# YOTSUBA_GNSS-UNIT_ver_1_0.net
KiCad netlist of a schematic drawn in EAGLE
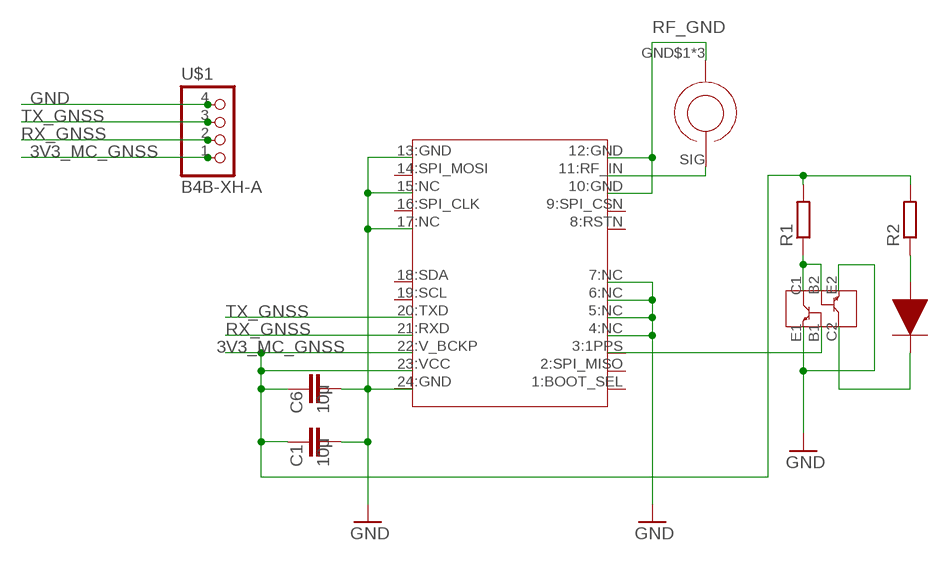
[diagram p0: schematic, sheet 1]

(export (version "E")
  (design (tool "Eeschema 10.0.6"))
  (components
    (comp (ref "C1")
      (value "10μ")
      (footprint "eagle-import:C2012")
      (libsource (lib "eagle-import") (part "C-EUC2012"))
    )
    (comp (ref "C6")
      (value "10μ")
      (footprint "eagle-import:C2012")
      (libsource (lib "eagle-import") (part "C-EUC2012"))
    )
    (comp (ref "ON/1PPS")
      (value "LED_1608")
      (footprint "eagle-import:LED_1608")
      (libsource (lib "eagle-import") (part "LED_1608"))
    )
    (comp (ref "R1")
      (value "R-EU_M2012")
      (footprint "eagle-import:M2012")
      (libsource (lib "eagle-import") (part "R-EU_M2012"))
    )
    (comp (ref "R2")
      (value "R-EU_M2012")
      (footprint "eagle-import:M2012")
      (libsource (lib "eagle-import") (part "R-EU_M2012"))
    )
    (comp (ref "U$1")
      (value "B4B-XH-A")
      (footprint "eagle-import:B4B-XH-A")
      (libsource (lib "eagle-import") (part "B4B-XH-A"))
    )
    (comp (ref "U$2")
      (value "ORION_B16")
      (footprint "eagle-import:ORION_B16")
      (libsource (lib "eagle-import") (part "ORION_B16"))
    )
    (comp (ref "U$3")
      (value "HN1C01FU")
      (footprint "eagle-import:SOT65P210X100-6N")
      (libsource (lib "eagle-import") (part "HN1C01FU"))
    )
    (comp (ref "U$5")
      (value "U.FL-R")
      (footprint "eagle-import:U.FL-R")
      (libsource (lib "eagle-import") (part "U.FL-R"))
    )
  )
  (nets
    (net (code "1") (name "/3V3_MC_GNSS") (class "Default")
      (node (ref "C1") (pin "1") (pinfunction "1_1") (pintype "passive"))
      (node (ref "C6") (pin "1") (pinfunction "1_1") (pintype "passive"))
      (node (ref "R1") (pin "2") (pinfunction "2_2") (pintype "passive"))
      (node (ref "R2") (pin "2") (pinfunction "2_2") (pintype "passive"))
      (node (ref "U$1") (pin "1") (pinfunction "1_1") (pintype "passive"))
      (node (ref "U$2") (pin "22:V_BCKP") (pinfunction "22:V_BCKP_22:V_BCKP") (pintype "bidirectional"))
      (node (ref "U$2") (pin "23:VCC") (pinfunction "23:VCC_23:VCC") (pintype "bidirectional"))
    )
    (net (code "2") (name "/RF_GND") (class "Default")
      (node (ref "U$2") (pin "10:GND") (pinfunction "10:GND_10:GND") (pintype "bidirectional"))
      (node (ref "U$2") (pin "12:GND") (pinfunction "12:GND_12:GND") (pintype "bidirectional"))
      (node (ref "U$5") (pin "GND$1") (pinfunction "GND_GND$1") (pintype "bidirectional"))
      (node (ref "U$5") (pin "GND$2") (pinfunction "GND_GND$2") (pintype "bidirectional"))
      (node (ref "U$5") (pin "GND$3") (pinfunction "GND_GND$3") (pintype "bidirectional"))
    )
    (net (code "3") (name "/RX_GNSS") (class "Default")
      (node (ref "U$1") (pin "2") (pinfunction "2_2") (pintype "passive"))
      (node (ref "U$2") (pin "21:RXD") (pinfunction "21:RXD_21:RXD") (pintype "bidirectional"))
    )
    (net (code "4") (name "/TX_GNSS") (class "Default")
      (node (ref "U$1") (pin "3") (pinfunction "3_3") (pintype "passive"))
      (node (ref "U$2") (pin "20:TXD") (pinfunction "20:TXD_20:TXD") (pintype "bidirectional"))
    )
    (net (code "5") (name "GND") (class "Default")
      (node (ref "C1") (pin "2") (pinfunction "2_2") (pintype "passive"))
      (node (ref "C6") (pin "2") (pinfunction "2_2") (pintype "passive"))
      (node (ref "U$1") (pin "4") (pinfunction "4_4") (pintype "passive"))
      (node (ref "U$2") (pin "13:GND") (pinfunction "13:GND_13:GND") (pintype "bidirectional"))
      (node (ref "U$2") (pin "15:NC") (pinfunction "15:NC_15:NC") (pintype "bidirectional"))
      (node (ref "U$2") (pin "17:NC") (pinfunction "17:NC_17:NC") (pintype "bidirectional"))
      (node (ref "U$2") (pin "24:GND") (pinfunction "24:GND_24:GND") (pintype "bidirectional"))
      (node (ref "U$2") (pin "4:NC") (pinfunction "4:NC_4:NC") (pintype "bidirectional"))
      (node (ref "U$2") (pin "5:NC") (pinfunction "5:NC_5:NC") (pintype "bidirectional"))
      (node (ref "U$2") (pin "6:NC") (pinfunction "6:NC_6:NC") (pintype "bidirectional"))
      (node (ref "U$2") (pin "7:NC") (pinfunction "7:NC_7:NC") (pintype "bidirectional"))
      (node (ref "U$3") (pin "E1") (pinfunction "E1_E1") (pintype "bidirectional"))
      (node (ref "U$3") (pin "E2") (pinfunction "E2_E2") (pintype "bidirectional"))
    )
    (net (code "6") (name "Net-(ON/1PPS-PadA)") (class "Default")
      (node (ref "ON/1PPS") (pin "A") (pinfunction "A_A") (pintype "bidirectional"))
      (node (ref "R2") (pin "1") (pinfunction "1_1") (pintype "passive"))
    )
    (net (code "7") (name "Net-(ON/1PPS-PadC)") (class "Default")
      (node (ref "ON/1PPS") (pin "C") (pinfunction "C_C") (pintype "bidirectional"))
      (node (ref "U$3") (pin "C2") (pinfunction "C2_C2") (pintype "bidirectional"))
    )
    (net (code "8") (name "Net-(R1-Pad1)") (class "Default")
      (node (ref "R1") (pin "1") (pinfunction "1_1") (pintype "passive"))
      (node (ref "U$3") (pin "B2") (pinfunction "B2_B2") (pintype "bidirectional"))
      (node (ref "U$3") (pin "C1") (pinfunction "C1_C1") (pintype "bidirectional"))
    )
    (net (code "9") (name "Net-(U$2-Pad3:1PPS)") (class "Default")
      (node (ref "U$2") (pin "3:1PPS") (pinfunction "3:1PPS_3:1PPS") (pintype "bidirectional"))
      (node (ref "U$3") (pin "B1") (pinfunction "B1_B1") (pintype "bidirectional"))
    )
    (net (code "10") (name "Net-(U$2-Pad11:RF_IN)") (class "Default")
      (node (ref "U$2") (pin "11:RF_IN") (pinfunction "11:RF_IN_11:RF_IN") (pintype "bidirectional"))
      (node (ref "U$5") (pin "SIG") (pinfunction "SIG_SIG") (pintype "bidirectional"))
    )
    (net (code "11") (name "unconnected-(U$2-Pad1:BOOT_SEL)") (class "Default")
      (node (ref "U$2") (pin "1:BOOT_SEL") (pinfunction "1:BOOT_SEL_1:BOOT_SEL") (pintype "bidirectional"))
    )
    (net (code "12") (name "unconnected-(U$2-Pad2:SPI_MISO)") (class "Default")
      (node (ref "U$2") (pin "2:SPI_MISO") (pinfunction "2:SPI_MISO_2:SPI_MISO") (pintype "bidirectional"))
    )
    (net (code "13") (name "unconnected-(U$2-Pad8:RSTN)") (class "Default")
      (node (ref "U$2") (pin "8:RSTN") (pinfunction "8:RSTN_8:RSTN") (pintype "bidirectional"))
    )
    (net (code "14") (name "unconnected-(U$2-Pad9:SPI_CSN)") (class "Default")
      (node (ref "U$2") (pin "9:SPI_CSN") (pinfunction "9:SPI_CSN_9:SPI_CSN") (pintype "bidirectional"))
    )
    (net (code "15") (name "unconnected-(U$2-Pad14:SPI_MOSI)") (class "Default")
      (node (ref "U$2") (pin "14:SPI_MOSI") (pinfunction "14:SPI_MOSI_14:SPI_MOSI") (pintype "bidirectional"))
    )
    (net (code "16") (name "unconnected-(U$2-Pad16:SPI_CLK)") (class "Default")
      (node (ref "U$2") (pin "16:SPI_CLK") (pinfunction "16:SPI_CLK_16:SPI_CLK") (pintype "bidirectional"))
    )
    (net (code "17") (name "unconnected-(U$2-Pad18:SDA)") (class "Default")
      (node (ref "U$2") (pin "18:SDA") (pinfunction "18:SDA_18:SDA") (pintype "bidirectional"))
    )
    (net (code "18") (name "unconnected-(U$2-Pad19:SCL)") (class "Default")
      (node (ref "U$2") (pin "19:SCL") (pinfunction "19:SCL_19:SCL") (pintype "bidirectional"))
    )
  )
)
